# ikoka-nano.net
KiCad netlist of a schematic drawn in EAGLE
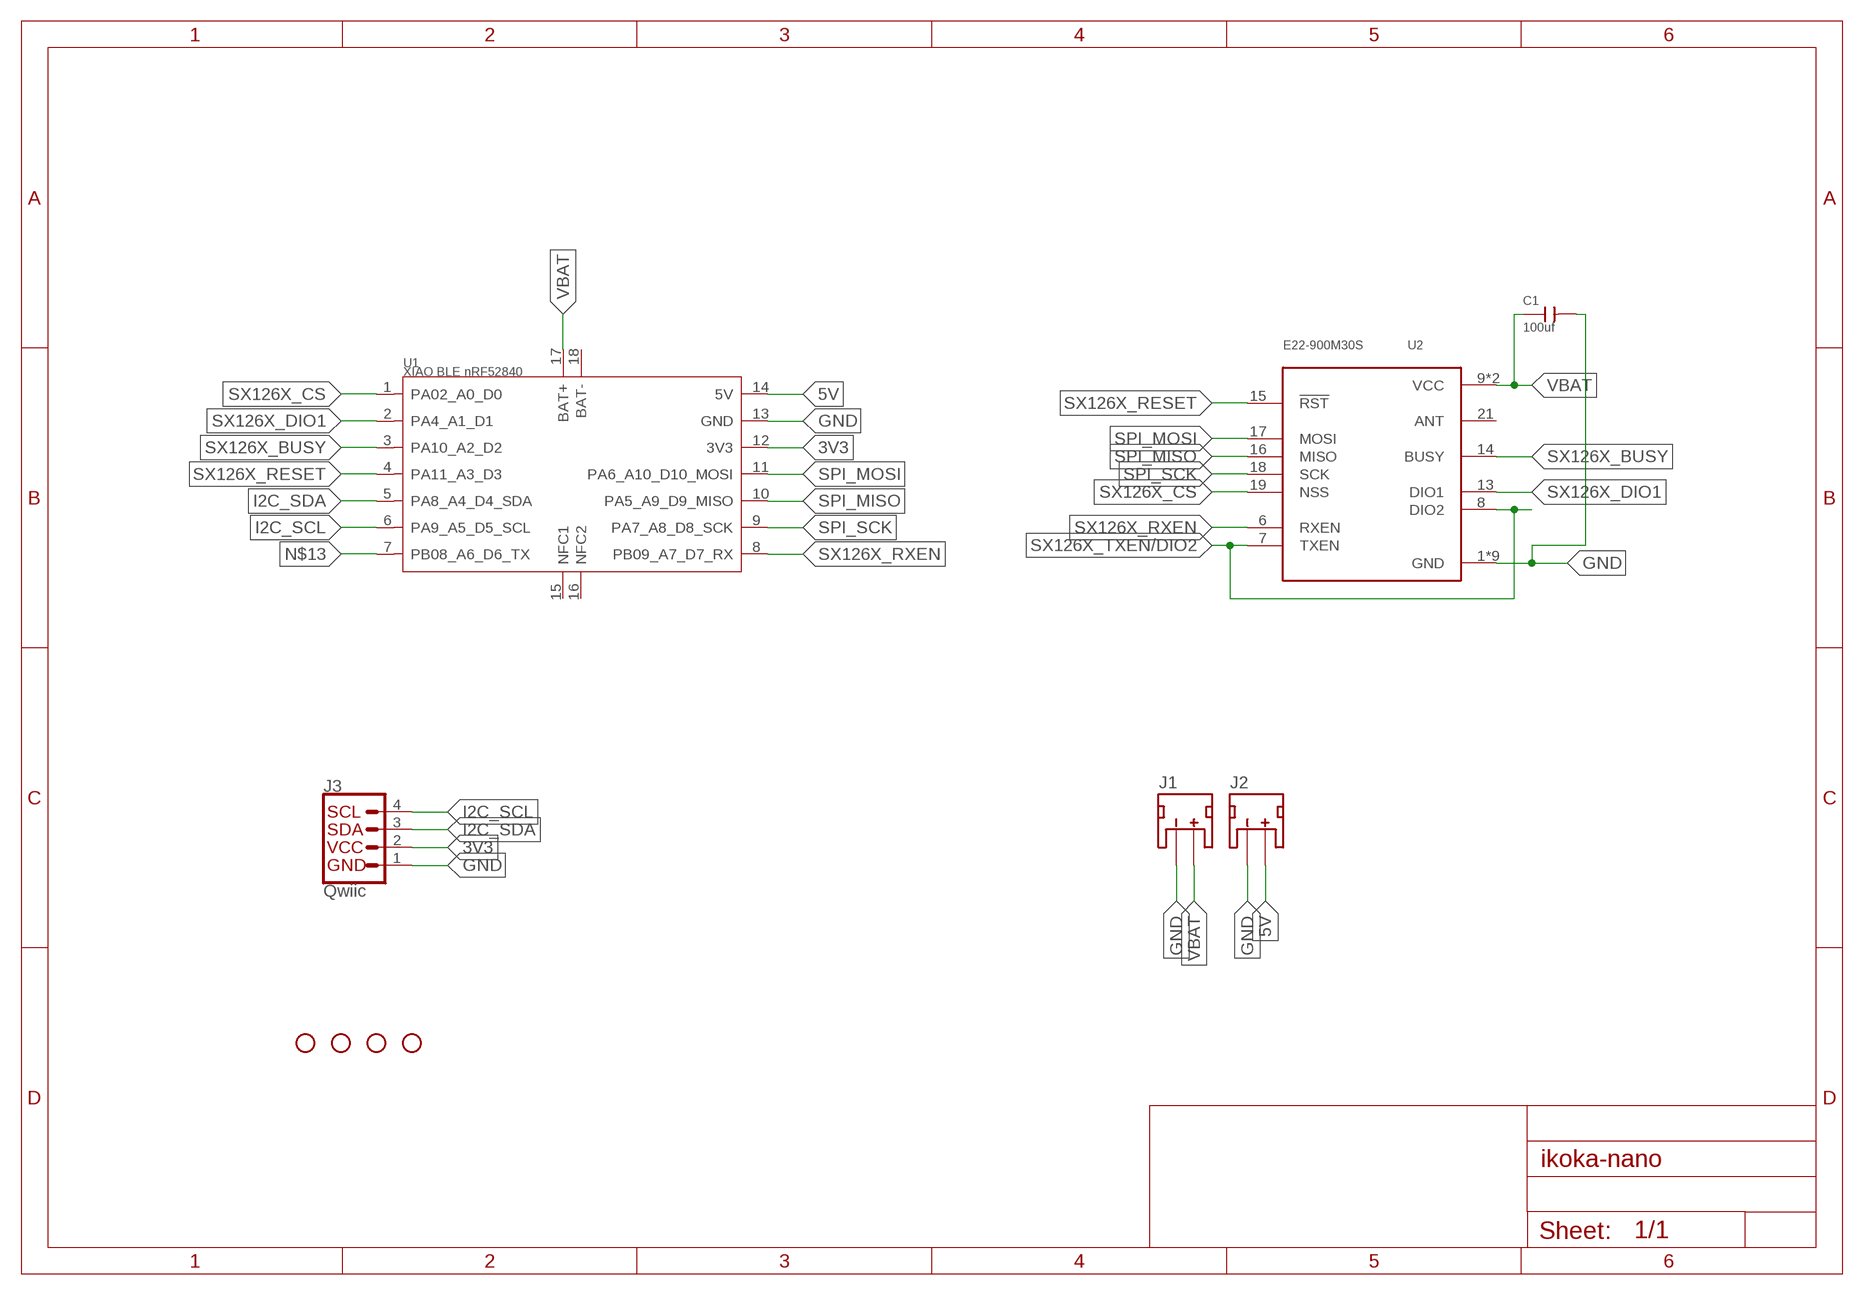
[diagram p0: schematic, sheet 1]

(export (version "E")
  (design (tool "Eeschema 10.0.6"))
  (components
    (comp (ref "C1")
      (value "100uf")
      (footprint "eagle-import:C1206")
      (fields (field (name "MPN") "GRM31CR60J107ME39L"))
      (libsource (lib "eagle-import") (part "CERAMIC-100UF-6.3V-20%-X5R(1206)"))
    )
    (comp (ref "H1")
      (value "STAND-OFF")
      (footprint "eagle-import:STAND-OFF")
      (libsource (lib "eagle-import") (part "STAND-OFF"))
    )
    (comp (ref "H2")
      (value "STAND-OFF")
      (footprint "eagle-import:STAND-OFF")
      (libsource (lib "eagle-import") (part "STAND-OFF"))
    )
    (comp (ref "H3")
      (value "STAND-OFF")
      (footprint "eagle-import:STAND-OFF")
      (libsource (lib "eagle-import") (part "STAND-OFF"))
    )
    (comp (ref "H4")
      (value "STAND-OFF")
      (footprint "eagle-import:STAND-OFF")
      (libsource (lib "eagle-import") (part "STAND-OFF"))
    )
    (comp (ref "J1")
      (value "LiPo 1S")
      (footprint "eagle-import:JST-2-SMD")
      (libsource (lib "eagle-import") (part "JST_2MM_MALE"))
    )
    (comp (ref "J2")
      (value "Solar ≤6.45V")
      (footprint "eagle-import:JST-2-SMD")
      (libsource (lib "eagle-import") (part "JST_2MM_MALE"))
    )
    (comp (ref "J3")
      (value "Qwiic")
      (footprint "eagle-import:JST04_1MM_RA")
      (libsource (lib "eagle-import") (part "QWIIC_CONNECTORJS-1MM"))
    )
    (comp (ref "U1")
      (value "XIAO BLE nRF52840")
      (footprint "eagle-import:MOUDLE16P-SMD-2.54-21X17.8MM")
      (libsource (lib "eagle-import") (part "MOUDLE-SEEEDUINO-XIAO-NRF52840-SMD"))
    )
    (comp (ref "U2")
      (value "E22-900M30S")
      (footprint "eagle-import:XCVR_E22-900M30S")
      (fields (field (name "MF") "EBYTE"))
      (libsource (lib "eagle-import") (part "E22-900M30S"))
    )
  )
  (nets
    (net (code "1") (name "3V3") (class "Default")
      (node (ref "J3") (pin "2") (pinfunction "2_2") (pintype "power_in"))
      (node (ref "U1") (pin "12") (pinfunction "3V3_12") (pintype "bidirectional"))
    )
    (net (code "2") (name "5V") (class "Default")
      (node (ref "J2") (pin "2") (pinfunction "+_2") (pintype "bidirectional"))
      (node (ref "U1") (pin "14") (pinfunction "5V_14") (pintype "bidirectional"))
    )
    (net (code "3") (name "GND") (class "Default")
      (node (ref "C1") (pin "2") (pinfunction "2_2") (pintype "passive"))
      (node (ref "J1") (pin "1") (pinfunction "-_1") (pintype "bidirectional"))
      (node (ref "J2") (pin "1") (pinfunction "-_1") (pintype "bidirectional"))
      (node (ref "J3") (pin "1") (pinfunction "1_1") (pintype "power_in"))
      (node (ref "U1") (pin "13") (pinfunction "GND_13") (pintype "bidirectional"))
      (node (ref "U2") (pin "1") (pinfunction "GND_1") (pintype "power_in"))
      (node (ref "U2") (pin "11") (pinfunction "GND_11") (pintype "power_in"))
      (node (ref "U2") (pin "12") (pinfunction "GND_12") (pintype "power_in"))
      (node (ref "U2") (pin "2") (pinfunction "GND_2") (pintype "power_in"))
      (node (ref "U2") (pin "20") (pinfunction "GND_20") (pintype "power_in"))
      (node (ref "U2") (pin "22") (pinfunction "GND_22") (pintype "power_in"))
      (node (ref "U2") (pin "3") (pinfunction "GND_3") (pintype "power_in"))
      (node (ref "U2") (pin "4") (pinfunction "GND_4") (pintype "power_in"))
      (node (ref "U2") (pin "5") (pinfunction "GND_5") (pintype "power_in"))
    )
    (net (code "4") (name "I2C_SCL") (class "Default")
      (node (ref "J3") (pin "4") (pinfunction "4_4") (pintype "passive"))
      (node (ref "U1") (pin "6") (pinfunction "PA9_A5_D5_SCL_6") (pintype "bidirectional"))
    )
    (net (code "5") (name "I2C_SDA") (class "Default")
      (node (ref "J3") (pin "3") (pinfunction "3_3") (pintype "passive"))
      (node (ref "U1") (pin "5") (pinfunction "PA8_A4_D4_SDA_5") (pintype "bidirectional"))
    )
    (net (code "6") (name "N$13") (class "Default")
      (node (ref "U1") (pin "7") (pinfunction "PB08_A6_D6_TX_7") (pintype "bidirectional"))
    )
    (net (code "7") (name "SPI_MISO") (class "Default")
      (node (ref "U1") (pin "10") (pinfunction "PA5_A9_D9_MISO_10") (pintype "bidirectional"))
      (node (ref "U2") (pin "16") (pinfunction "MISO_16") (pintype "output"))
    )
    (net (code "8") (name "SPI_MOSI") (class "Default")
      (node (ref "U1") (pin "11") (pinfunction "PA6_A10_D10_MOSI_11") (pintype "bidirectional"))
      (node (ref "U2") (pin "17") (pinfunction "MOSI_17") (pintype "input"))
    )
    (net (code "9") (name "SPI_SCK") (class "Default")
      (node (ref "U1") (pin "9") (pinfunction "PA7_A8_D8_SCK_9") (pintype "bidirectional"))
      (node (ref "U2") (pin "18") (pinfunction "SCK_18") (pintype "input"))
    )
    (net (code "10") (name "SX126X_BUSY") (class "Default")
      (node (ref "U1") (pin "3") (pinfunction "PA10_A2_D2_3") (pintype "bidirectional"))
      (node (ref "U2") (pin "14") (pinfunction "BUSY_14") (pintype "output"))
    )
    (net (code "11") (name "SX126X_CS") (class "Default")
      (node (ref "U1") (pin "1") (pinfunction "PA02_A0_D0_1") (pintype "bidirectional"))
      (node (ref "U2") (pin "19") (pinfunction "NSS_19") (pintype "input"))
    )
    (net (code "12") (name "SX126X_DIO1") (class "Default")
      (node (ref "U1") (pin "2") (pinfunction "PA4_A1_D1_2") (pintype "bidirectional"))
      (node (ref "U2") (pin "13") (pinfunction "DIO1_13") (pintype "bidirectional"))
    )
    (net (code "13") (name "SX126X_RESET") (class "Default")
      (node (ref "U1") (pin "4") (pinfunction "PA11_A3_D3_4") (pintype "bidirectional"))
      (node (ref "U2") (pin "15") (pinfunction "~{RST}_15") (pintype "input"))
    )
    (net (code "14") (name "SX126X_RXEN") (class "Default")
      (node (ref "U1") (pin "8") (pinfunction "PB09_A7_D7_RX_8") (pintype "bidirectional"))
      (node (ref "U2") (pin "6") (pinfunction "RXEN_6") (pintype "input"))
    )
    (net (code "15") (name "SX126X_TXEN{slash}DIO2") (class "Default")
      (node (ref "U2") (pin "7") (pinfunction "TXEN_7") (pintype "input"))
      (node (ref "U2") (pin "8") (pinfunction "DIO2_8") (pintype "bidirectional"))
    )
    (net (code "16") (name "VBAT") (class "Default")
      (node (ref "C1") (pin "1") (pinfunction "1_1") (pintype "passive"))
      (node (ref "J1") (pin "2") (pinfunction "+_2") (pintype "bidirectional"))
      (node (ref "U1") (pin "17") (pinfunction "BAT+_17") (pintype "bidirectional"))
      (node (ref "U2") (pin "10") (pinfunction "VCC_10") (pintype "power_in"))
      (node (ref "U2") (pin "9") (pinfunction "VCC_9") (pintype "power_in"))
    )
    (net (code "17") (name "unconnected-(J1-PAD1-PadNC1)") (class "Default")
      (node (ref "J1") (pin "NC1") (pinfunction "PAD1_NC1") (pintype "bidirectional"))
    )
    (net (code "18") (name "unconnected-(J1-PAD2-PadNC2)") (class "Default")
      (node (ref "J1") (pin "NC2") (pinfunction "PAD2_NC2") (pintype "bidirectional"))
    )
    (net (code "19") (name "unconnected-(J2-PAD1-PadNC1)") (class "Default")
      (node (ref "J2") (pin "NC1") (pinfunction "PAD1_NC1") (pintype "bidirectional"))
    )
    (net (code "20") (name "unconnected-(J2-PAD2-PadNC2)") (class "Default")
      (node (ref "J2") (pin "NC2") (pinfunction "PAD2_NC2") (pintype "bidirectional"))
    )
    (net (code "21") (name "unconnected-(U1-BAT--Pad18)") (class "Default")
      (node (ref "U1") (pin "18") (pinfunction "BAT-_18") (pintype "bidirectional"))
    )
    (net (code "22") (name "unconnected-(U1-NFC1-Pad15)") (class "Default")
      (node (ref "U1") (pin "15") (pinfunction "NFC1_15") (pintype "bidirectional"))
    )
    (net (code "23") (name "unconnected-(U1-NFC2-Pad16)") (class "Default")
      (node (ref "U1") (pin "16") (pinfunction "NFC2_16") (pintype "bidirectional"))
    )
    (net (code "24") (name "unconnected-(U2-ANT-Pad21)") (class "Default")
      (node (ref "U2") (pin "21") (pinfunction "ANT_21") (pintype "output"))
    )
  )
)
